# TSOP_Module.net
KiCad netlist of a schematic drawn in EasyEDA
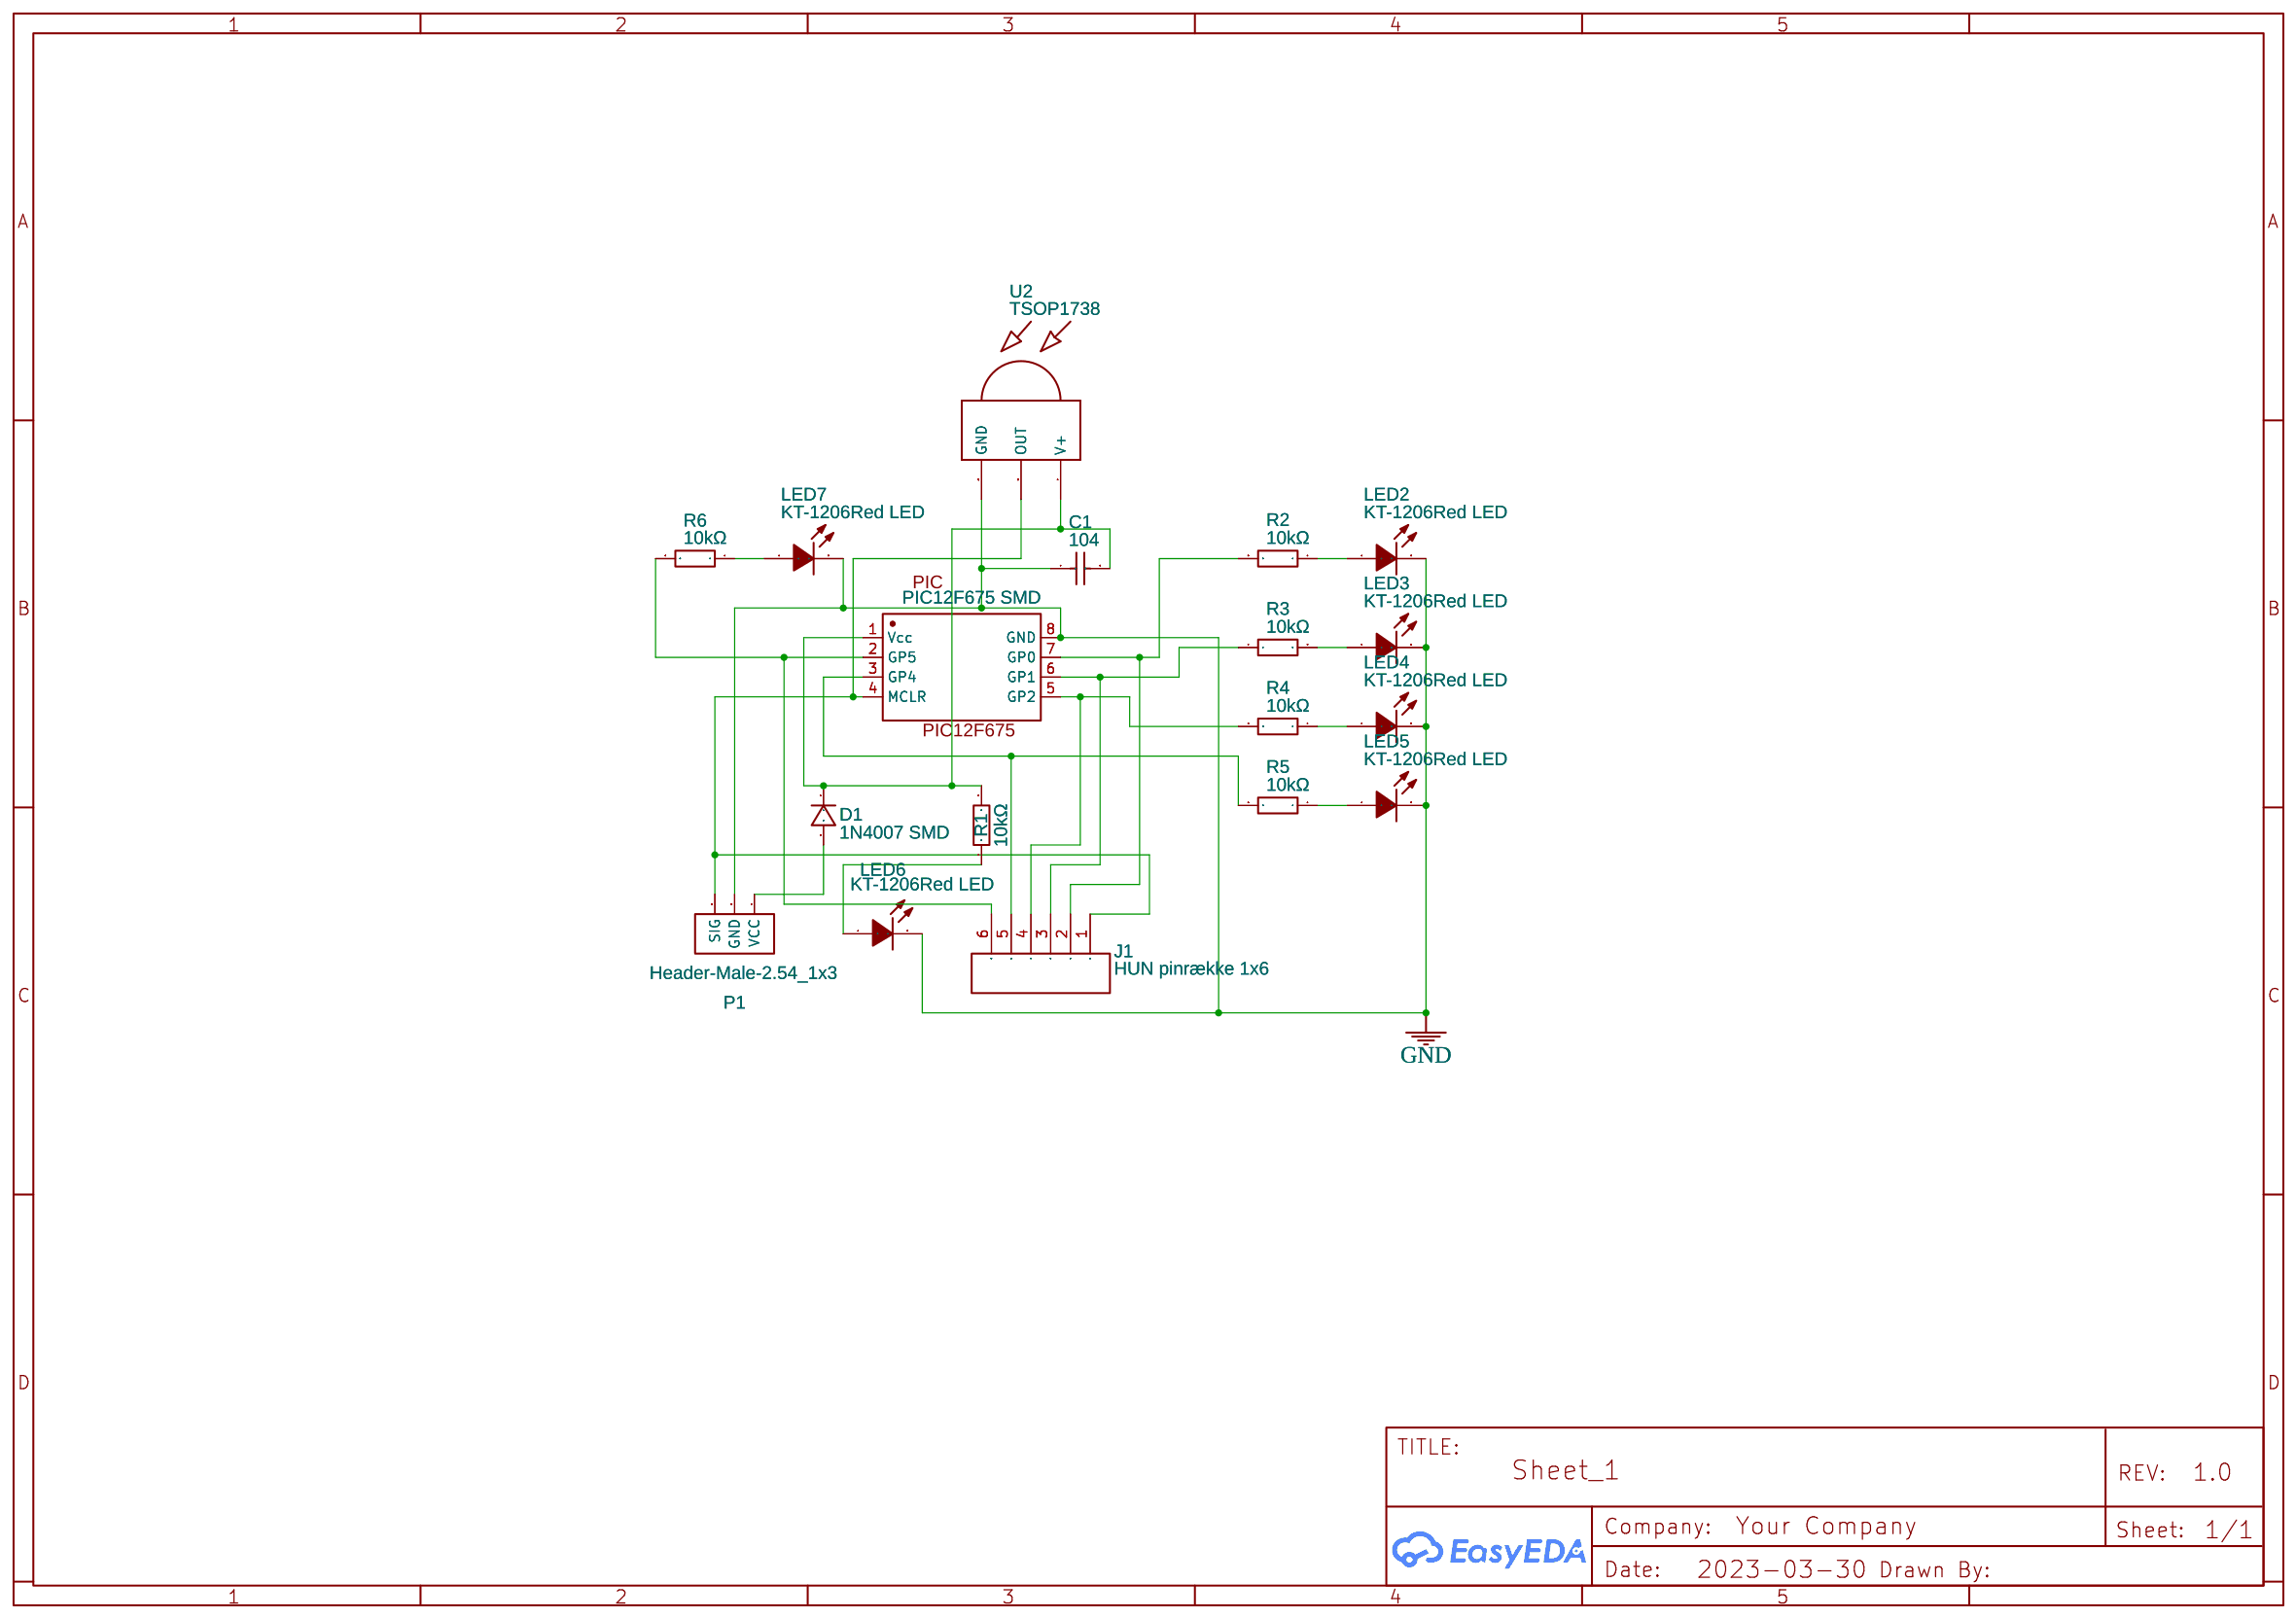
[diagram p0: Circuit 1]
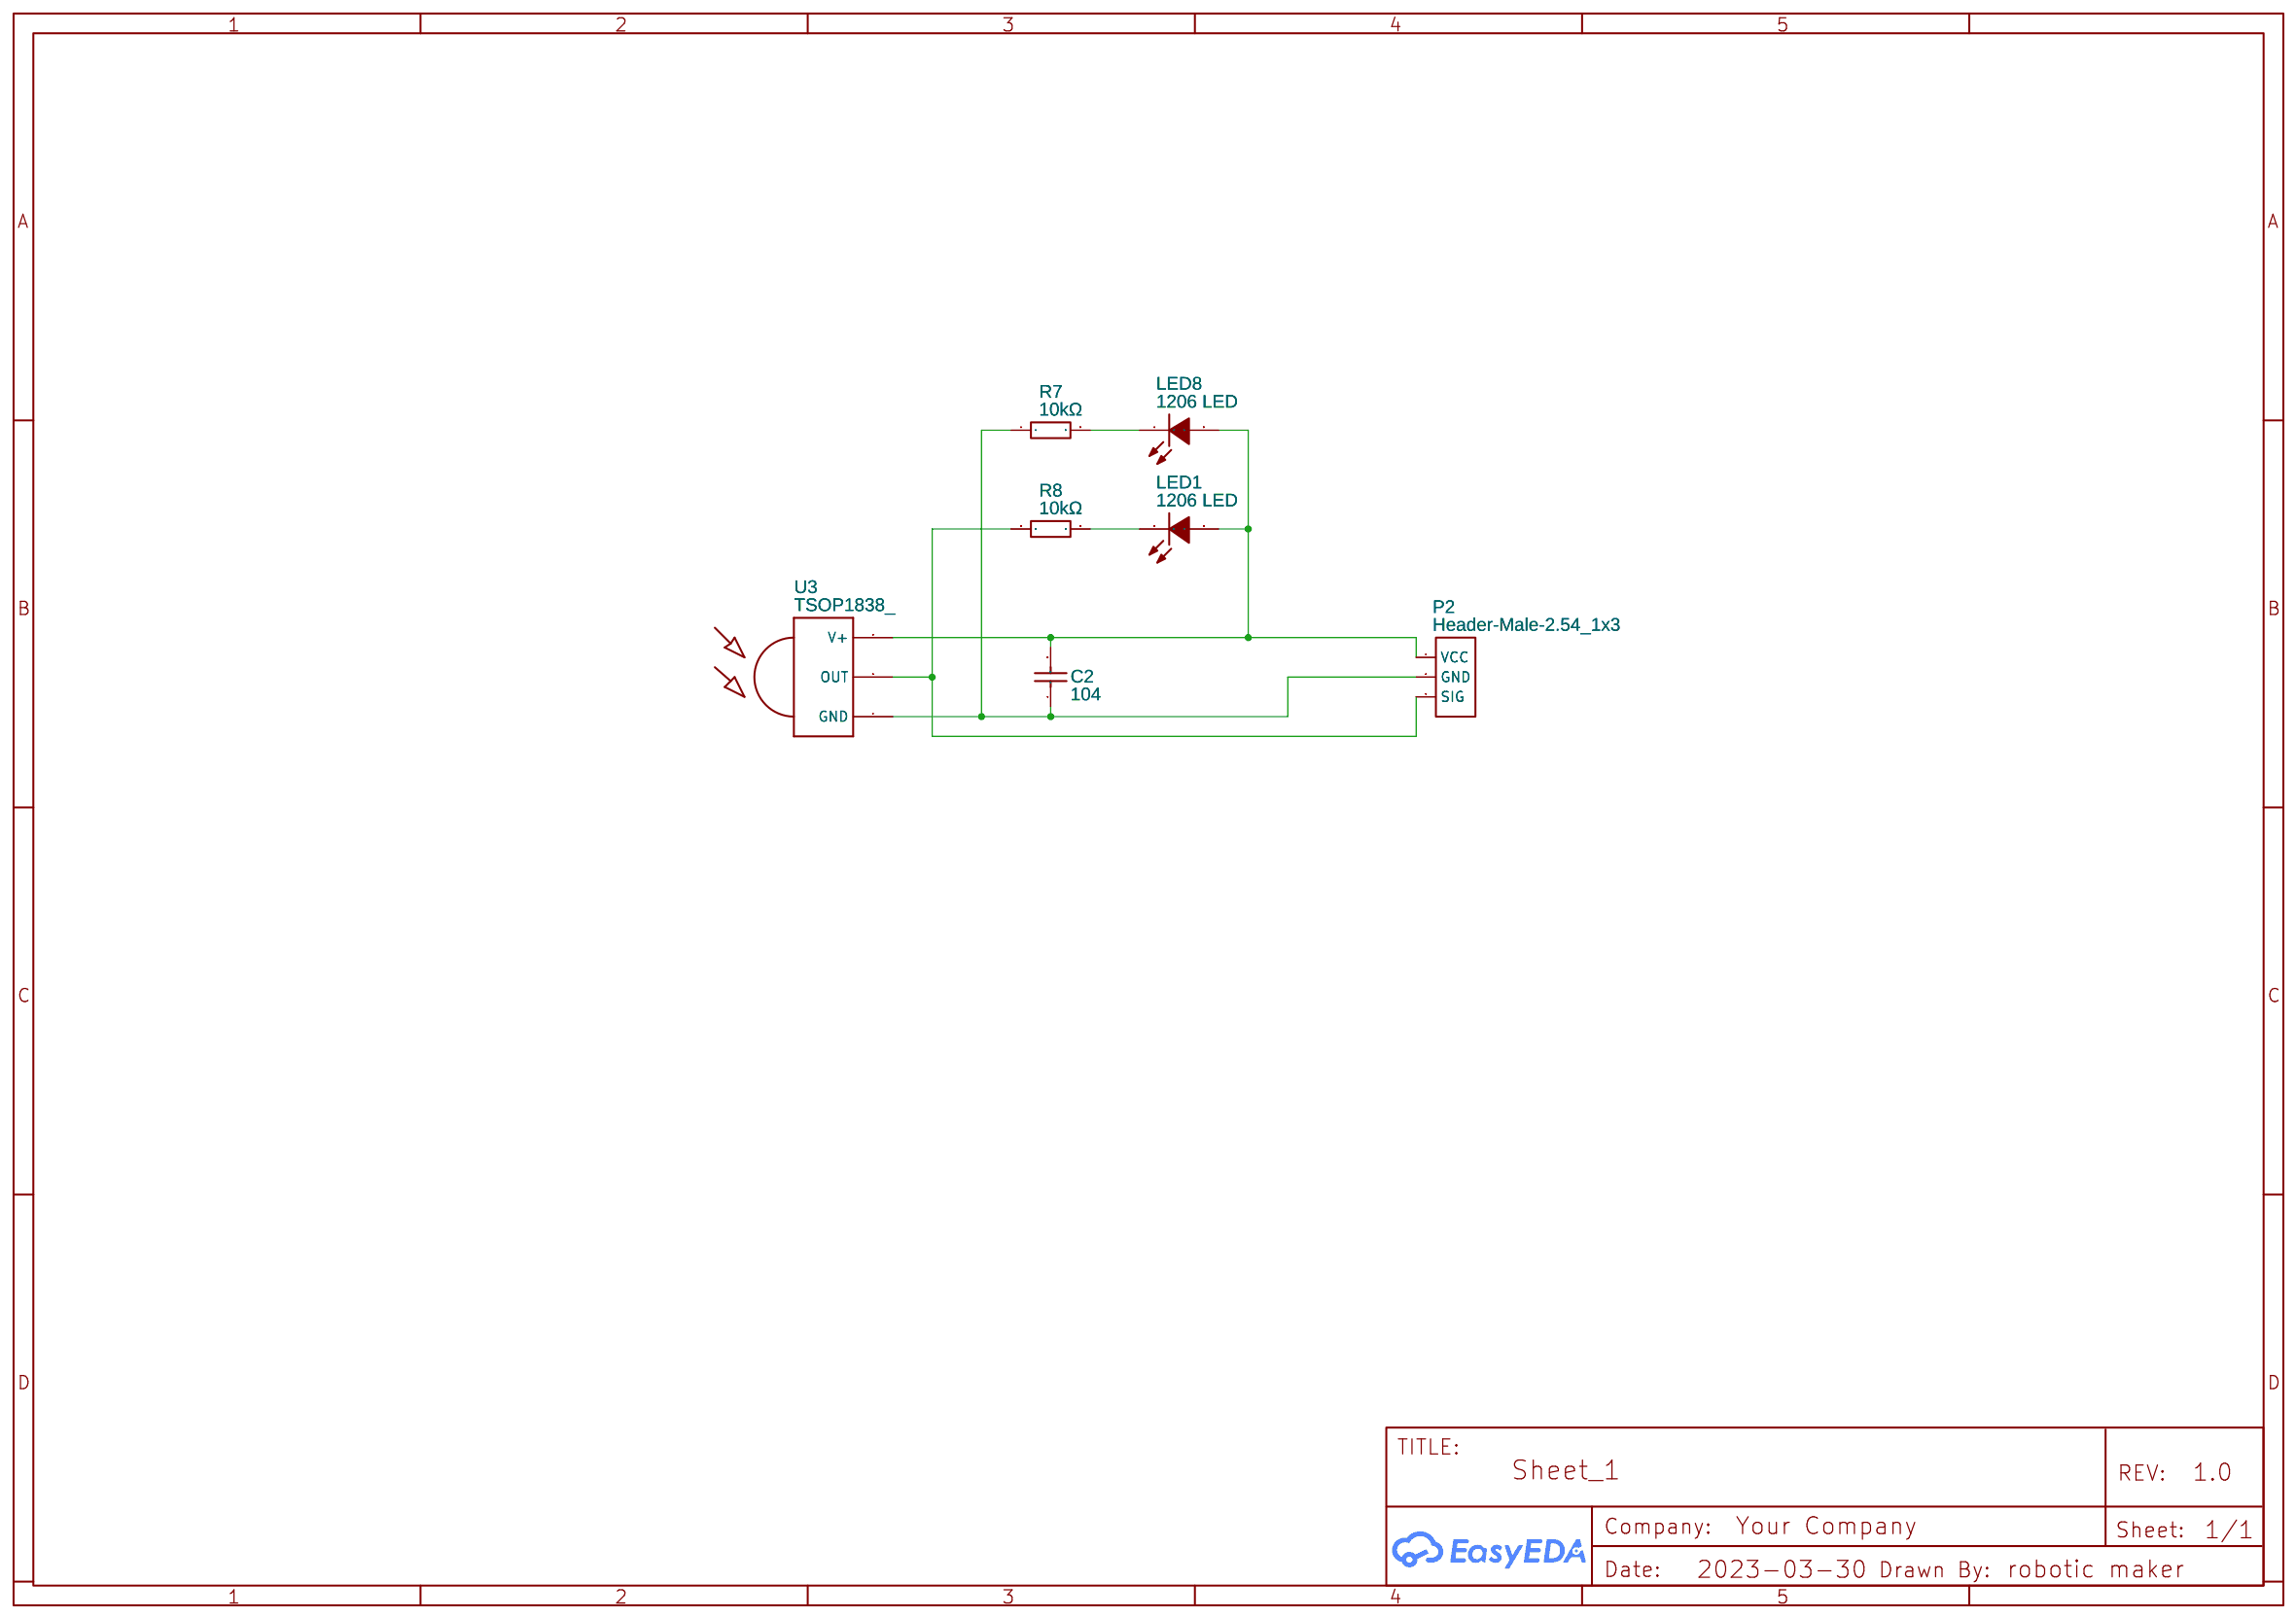
[diagram p1: Circuit 2]

(export (version "E")
  (design (tool "Eeschema 10.0.6"))
  (components
    (comp (ref "C1")
      (value "104")
      (fields
        (field (name "BOM_Manufacturer Part") "100pF250VNP0")
        (field (name "BOM_Supplier Part") "C27260")
      )
      (libsource (lib "") (part "104PF"))
    )
    (comp (ref "D1")
      (value "1N4007 SMD")
      (fields (field (name "BOM_Manufacturer Part") "1N4007") (field (name "BOM_Supplier Part") "C126233"))
      (libsource (lib "") (part "1N4007 SMD"))
    )
    (comp (ref "J1")
      (value "HUN pinrække 1x6")
      (fields (field (name "BOM_Manufacturer Part") "New SchematicLib"))
      (libsource (lib "") (part "HUN pinrække 1x6"))
    )
    (comp (ref "LED2")
      (value "KT-1206Red LED")
      (fields (field (name "BOM_Supplier Part") "C49018"))
      (libsource (lib "") (part "KT-1206Red LED"))
    )
    (comp (ref "LED3")
      (value "KT-1206Red LED")
      (fields (field (name "BOM_Supplier Part") "C49018"))
      (libsource (lib "") (part "KT-1206Red LED"))
    )
    (comp (ref "LED4")
      (value "KT-1206Red LED")
      (fields (field (name "BOM_Supplier Part") "C49018"))
      (libsource (lib "") (part "KT-1206Red LED"))
    )
    (comp (ref "LED5")
      (value "KT-1206Red LED")
      (fields (field (name "BOM_Supplier Part") "C49018"))
      (libsource (lib "") (part "KT-1206Red LED"))
    )
    (comp (ref "LED6")
      (value "KT-1206Red LED")
      (fields (field (name "BOM_Supplier Part") "C49018"))
      (libsource (lib "") (part "KT-1206Red LED"))
    )
    (comp (ref "LED7")
      (value "KT-1206Red LED")
      (fields (field (name "BOM_Supplier Part") "C49018"))
      (libsource (lib "") (part "KT-1206Red LED"))
    )
    (comp (ref "P1")
      (value "Header-Male-2.54_1x3")
      (fields
        (field (name "BOM_Manufacturer Part") "2.54-1*3P母")
        (field (name "BOM_Supplier Part") "C146243")
      )
      (libsource (lib "") (part "Header-Female-2.54_1x3"))
    )
    (comp (ref "R1")
      (value "10kΩ")
      (fields
        (field (name "BOM_Manufacturer Part") "RMC120610K5%N")
        (field (name "BOM_Supplier Part") "C269752")
      )
      (libsource (lib "") (part "RMC120610K5%N_2"))
    )
    (comp (ref "R2")
      (value "10kΩ")
      (fields
        (field (name "BOM_Manufacturer Part") "RMC120610K5%N")
        (field (name "BOM_Supplier Part") "C269752")
      )
      (libsource (lib "") (part "RMC120610K5%N"))
    )
    (comp (ref "R3")
      (value "10kΩ")
      (fields
        (field (name "BOM_Manufacturer Part") "RMC120610K5%N")
        (field (name "BOM_Supplier Part") "C269752")
      )
      (libsource (lib "") (part "RMC120610K5%N_1"))
    )
    (comp (ref "R4")
      (value "10kΩ")
      (fields
        (field (name "BOM_Manufacturer Part") "RMC120610K5%N")
        (field (name "BOM_Supplier Part") "C269752")
      )
      (libsource (lib "") (part "RMC120610K5%N"))
    )
    (comp (ref "R5")
      (value "10kΩ")
      (fields
        (field (name "BOM_Manufacturer Part") "RMC120610K5%N")
        (field (name "BOM_Supplier Part") "C269752")
      )
      (libsource (lib "") (part "RMC120610K5%N"))
    )
    (comp (ref "R6")
      (value "10kΩ")
      (fields
        (field (name "BOM_Manufacturer Part") "RMC120610K5%N")
        (field (name "BOM_Supplier Part") "C269752")
      )
      (libsource (lib "") (part "RMC120610K5%N"))
    )
    (comp (ref "U1") (value "PIC12F675 SMD") (libsource (lib "") (part "PIC12F675 SMD")))
    (comp (ref "U2") (value "TSOP1738") (libsource (lib "") (part "TSOP1738")))
    (comp (ref "C2")
      (value "104")
      (fields
        (field (name "BOM_Manufacturer Part") "100pF250VNP0")
        (field (name "BOM_Supplier Part") "C27260")
      )
      (libsource (lib "") (part "104PF"))
    )
    (comp (ref "LED1")
      (value "1206 LED")
      (fields (field (name "BOM_Supplier Part") "1206"))
      (libsource (lib "") (part "1206 LED"))
    )
    (comp (ref "LED8")
      (value "1206 LED")
      (fields (field (name "BOM_Supplier Part") "1206"))
      (libsource (lib "") (part "1206 LED"))
    )
    (comp (ref "P2")
      (value "Header-Male-2.54_1x3")
      (fields
        (field (name "BOM_Manufacturer Part") "2.54-1*3P母")
        (field (name "BOM_Supplier Part") "C146243")
      )
      (libsource (lib "") (part "Header-Female-2.54_1x3"))
    )
    (comp (ref "R7")
      (value "10kΩ")
      (fields
        (field (name "BOM_Manufacturer Part") "RMC120610K5%N")
        (field (name "BOM_Supplier Part") "C269752")
      )
      (libsource (lib "") (part "RMC120610K5%N"))
    )
    (comp (ref "R8")
      (value "10kΩ")
      (fields
        (field (name "BOM_Manufacturer Part") "RMC120610K5%N")
        (field (name "BOM_Supplier Part") "C269752")
      )
      (libsource (lib "") (part "RMC120610K5%N"))
    )
    (comp (ref "U3") (value "TSOP1838_") (libsource (lib "") (part "TSOP1838_")))
  )
  (nets
    (net (code "1") (name "GND") (class "Default")
      (node (ref "C1") (pin "1") (pinfunction "1_1") (pintype "input"))
      (node (ref "LED2") (pin "2") (pinfunction "K_2") (pintype "unspecified"))
      (node (ref "LED3") (pin "2") (pinfunction "K_2") (pintype "unspecified"))
      (node (ref "LED4") (pin "2") (pinfunction "K_2") (pintype "unspecified"))
      (node (ref "LED5") (pin "2") (pinfunction "K_2") (pintype "unspecified"))
      (node (ref "LED6") (pin "2") (pinfunction "K_2") (pintype "unspecified"))
      (node (ref "LED7") (pin "2") (pinfunction "K_2") (pintype "unspecified"))
      (node (ref "P1") (pin "2") (pinfunction "GND_2") (pintype "input"))
      (node (ref "U1") (pin "8") (pinfunction "GND_8") (pintype "unspecified"))
      (node (ref "U2") (pin "GND") (pinfunction "GND_GND") (pintype "unspecified"))
    )
    (net (code "2") (name "Net-(LED1-A)") (class "Default")
      (node (ref "C2") (pin "2") (pinfunction "2_2") (pintype "input"))
      (node (ref "LED1") (pin "2") (pinfunction "A_2") (pintype "unspecified"))
      (node (ref "LED8") (pin "2") (pinfunction "A_2") (pintype "unspecified"))
      (node (ref "P2") (pin "1") (pinfunction "VCC_1") (pintype "input"))
      (node (ref "U3") (pin "3") (pinfunction "V+_3") (pintype "unspecified"))
    )
    (net (code "3") (name "Net-(LED1-K)") (class "Default")
      (node (ref "LED1") (pin "1") (pinfunction "K_1") (pintype "unspecified"))
      (node (ref "R8") (pin "2") (pinfunction "2_2") (pintype "unspecified"))
    )
    (net (code "4") (name "Net-(LED2-A)") (class "Default")
      (node (ref "LED2") (pin "1") (pinfunction "A_1") (pintype "unspecified"))
      (node (ref "R2") (pin "1") (pinfunction "1_1") (pintype "unspecified"))
    )
    (net (code "5") (name "Net-(LED3-A)") (class "Default")
      (node (ref "LED3") (pin "1") (pinfunction "A_1") (pintype "unspecified"))
      (node (ref "R3") (pin "2") (pinfunction "2_2") (pintype "unspecified"))
    )
    (net (code "6") (name "Net-(LED4-A)") (class "Default")
      (node (ref "LED4") (pin "1") (pinfunction "A_1") (pintype "unspecified"))
      (node (ref "R4") (pin "1") (pinfunction "1_1") (pintype "unspecified"))
    )
    (net (code "7") (name "Net-(LED5-A)") (class "Default")
      (node (ref "LED5") (pin "1") (pinfunction "A_1") (pintype "unspecified"))
      (node (ref "R5") (pin "1") (pinfunction "1_1") (pintype "unspecified"))
    )
    (net (code "8") (name "Net-(LED6-A)") (class "Default")
      (node (ref "LED6") (pin "1") (pinfunction "A_1") (pintype "unspecified"))
      (node (ref "R1") (pin "1") (pinfunction "1_1") (pintype "unspecified"))
    )
    (net (code "9") (name "Net-(LED7-A)") (class "Default")
      (node (ref "LED7") (pin "1") (pinfunction "A_1") (pintype "unspecified"))
      (node (ref "R6") (pin "1") (pinfunction "1_1") (pintype "unspecified"))
    )
    (net (code "10") (name "Net-(LED8-K)") (class "Default")
      (node (ref "LED8") (pin "1") (pinfunction "K_1") (pintype "unspecified"))
      (node (ref "R7") (pin "2") (pinfunction "2_2") (pintype "unspecified"))
    )
    (net (code "11") (name "Net-(P1-SIG)") (class "Default")
      (node (ref "J1") (pin "1") (pinfunction "1_1") (pintype "unspecified"))
      (node (ref "P1") (pin "3") (pinfunction "SIG_3") (pintype "input"))
      (node (ref "U1") (pin "4") (pinfunction "MCLR_4") (pintype "unspecified"))
      (node (ref "U2") (pin "OUT") (pinfunction "OUT_OUT") (pintype "unspecified"))
    )
    (net (code "12") (name "Net-(P1-VCC)") (class "Default")
      (node (ref "D1") (pin "2") (pinfunction "2_2") (pintype "unspecified"))
      (node (ref "P1") (pin "1") (pinfunction "VCC_1") (pintype "input"))
    )
    (net (code "13") (name "Net-(P2-GND)") (class "Default")
      (node (ref "C2") (pin "1") (pinfunction "1_1") (pintype "input"))
      (node (ref "P2") (pin "2") (pinfunction "GND_2") (pintype "input"))
      (node (ref "R7") (pin "1") (pinfunction "1_1") (pintype "unspecified"))
      (node (ref "U3") (pin "1") (pinfunction "GND_1") (pintype "unspecified"))
    )
    (net (code "14") (name "Net-(P2-SIG)") (class "Default")
      (node (ref "P2") (pin "3") (pinfunction "SIG_3") (pintype "input"))
      (node (ref "R8") (pin "1") (pinfunction "1_1") (pintype "unspecified"))
      (node (ref "U3") (pin "2") (pinfunction "OUT_2") (pintype "unspecified"))
    )
    (net (code "15") (name "Net-(U1-GP0)") (class "Default")
      (node (ref "J1") (pin "2") (pinfunction "2_2") (pintype "unspecified"))
      (node (ref "R2") (pin "2") (pinfunction "2_2") (pintype "unspecified"))
      (node (ref "U1") (pin "7") (pinfunction "GP0_7") (pintype "unspecified"))
    )
    (net (code "16") (name "Net-(U1-GP1)") (class "Default")
      (node (ref "J1") (pin "3") (pinfunction "3_3") (pintype "unspecified"))
      (node (ref "R3") (pin "1") (pinfunction "1_1") (pintype "unspecified"))
      (node (ref "U1") (pin "6") (pinfunction "GP1_6") (pintype "unspecified"))
    )
    (net (code "17") (name "Net-(U1-GP2)") (class "Default")
      (node (ref "J1") (pin "4") (pinfunction "4_4") (pintype "unspecified"))
      (node (ref "R4") (pin "2") (pinfunction "2_2") (pintype "unspecified"))
      (node (ref "U1") (pin "5") (pinfunction "GP2_5") (pintype "unspecified"))
    )
    (net (code "18") (name "Net-(U1-GP4)") (class "Default")
      (node (ref "J1") (pin "5") (pinfunction "5_5") (pintype "unspecified"))
      (node (ref "R5") (pin "2") (pinfunction "2_2") (pintype "unspecified"))
      (node (ref "U1") (pin "3") (pinfunction "GP4_3") (pintype "unspecified"))
    )
    (net (code "19") (name "Net-(U1-GP5)") (class "Default")
      (node (ref "J1") (pin "6") (pinfunction "6_6") (pintype "unspecified"))
      (node (ref "R6") (pin "2") (pinfunction "2_2") (pintype "unspecified"))
      (node (ref "U1") (pin "2") (pinfunction "GP5_2") (pintype "unspecified"))
    )
    (net (code "20") (name "Net-(U1-Vcc)") (class "Default")
      (node (ref "C1") (pin "2") (pinfunction "2_2") (pintype "input"))
      (node (ref "D1") (pin "1") (pinfunction "1_1") (pintype "unspecified"))
      (node (ref "R1") (pin "2") (pinfunction "2_2") (pintype "unspecified"))
      (node (ref "U1") (pin "1") (pinfunction "Vcc_1") (pintype "unspecified"))
      (node (ref "U2") (pin "V+") (pinfunction "V+_V+") (pintype "unspecified"))
    )
  )
)
